# design.net
KiCad netlist of a schematic drawn in Altium Designer
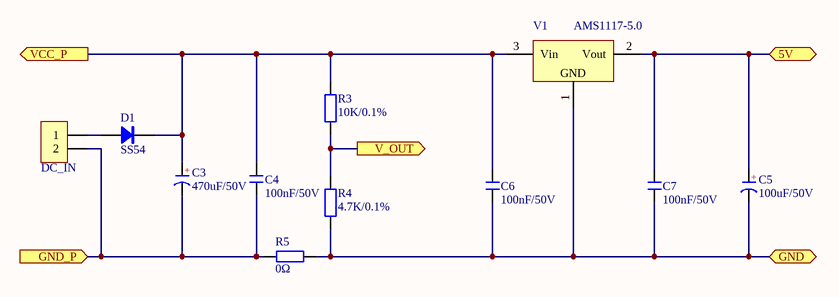
[diagram p0: 电机电源输入原理图.SchDoc]

(export (version "E")
  (design (tool "Eeschema 10.0.6"))
  (components
    (comp (ref "C3")
      (value "470uF/50V")
      (footprint "CAP 5.0*12.5*20")
      (description "直插电解电容")
      (fields (field (name "版权归属") "源创客"))
      (libsource (lib "3.1   - 电阻-电容-电感") (part "C-CAP"))
    )
    (comp (ref "C4")
      (value "100nF/50V")
      (footprint "C 0603_M")
      (description "无极性贴片电容")
      (fields (field (name "版权归属") "源创客"))
      (libsource (lib "3.1   - 电阻-电容-电感") (part "C"))
    )
    (comp (ref "C5")
      (value "100uF/50V")
      (footprint "CAP 3.5*8*11.5")
      (description "直插电解电容")
      (fields (field (name "版权归属") "源创客"))
      (libsource (lib "3.1   - 电阻-电容-电感") (part "C-CAP"))
    )
    (comp (ref "C6")
      (value "100nF/50V")
      (footprint "C 0603_M")
      (description "无极性贴片电容")
      (fields (field (name "版权归属") "源创客"))
      (libsource (lib "3.1   - 电阻-电容-电感") (part "C"))
    )
    (comp (ref "C7")
      (value "100nF/50V")
      (footprint "C 0603_M")
      (description "无极性贴片电容")
      (fields (field (name "版权归属") "源创客"))
      (libsource (lib "3.1   - 电阻-电容-电感") (part "C"))
    )
    (comp (ref "D1")
      (value "SS54")
      (footprint "SMA")
      (description "肖特基二极管")
      (fields (field (name "版权归属") "源创客"))
      (libsource (lib "8.1   - 二极管-整流桥") (part "SS24"))
    )
    (comp (ref "DC_IN")
      (value "HDR-1X2")
      (footprint "XT30PW-M公头")
      (description "2P接插件")
      (fields (field (name "版权归属") "源创客"))
      (libsource (lib "4.10 - 接插件-脚距5.0") (part "Header 2"))
    )
    (comp (ref "R3")
      (value "10K/0.1%")
      (footprint "R 0603_M")
      (description "贴片电阻")
      (fields (field (name "版权归属") "源创客"))
      (libsource (lib "3.1   - 电阻-电容-电感") (part "R"))
    )
    (comp (ref "R4")
      (value "4.7K/0.1%")
      (footprint "R 0603_M")
      (description "贴片电阻")
      (fields (field (name "版权归属") "源创客"))
      (libsource (lib "3.1   - 电阻-电容-电感") (part "R"))
    )
    (comp (ref "R5")
      (value "0Ω")
      (footprint "R 0805_M")
      (description "贴片电阻")
      (fields (field (name "版权归属") "源创客"))
      (libsource (lib "3.1   - 电阻-电容-电感") (part "R"))
    )
    (comp (ref "V1")
      (value "AMS1117-5.0")
      (footprint "SOT89_N")
      (description "三端稳压芯片")
      (fields (field (name "版权归属") "源创客"))
      (libsource (lib "1.3   - 电源类芯片") (part "AMS1117"))
    )
  )
  (nets
    (net (code "1") (name "/5V") (class "Default")
      (node (ref "C5") (pin "1") (pinfunction "A_1") (pintype "passive"))
      (node (ref "C7") (pin "2") (pinfunction "2_2") (pintype "passive"))
      (node (ref "V1") (pin "2") (pinfunction "Vout_2") (pintype "passive"))
    )
    (net (code "2") (name "/GND") (class "Default")
      (node (ref "C5") (pin "2") (pinfunction "K_2") (pintype "passive"))
      (node (ref "C6") (pin "1") (pinfunction "1_1") (pintype "passive"))
      (node (ref "C7") (pin "1") (pinfunction "1_1") (pintype "passive"))
      (node (ref "R4") (pin "1") (pinfunction "1_1") (pintype "passive"))
      (node (ref "R5") (pin "1") (pinfunction "1_1") (pintype "passive"))
      (node (ref "V1") (pin "1") (pinfunction "GND_1") (pintype "passive"))
    )
    (net (code "3") (name "/GND_P") (class "Default")
      (node (ref "C3") (pin "2") (pinfunction "K_2") (pintype "passive"))
      (node (ref "C4") (pin "1") (pinfunction "1_1") (pintype "passive"))
      (node (ref "DC_IN") (pin "2") (pinfunction "2_2") (pintype "passive"))
      (node (ref "R5") (pin "2") (pinfunction "2_2") (pintype "passive"))
    )
    (net (code "4") (name "/VCC_P") (class "Default")
      (node (ref "C3") (pin "1") (pinfunction "A_1") (pintype "passive"))
      (node (ref "C4") (pin "2") (pinfunction "2_2") (pintype "passive"))
      (node (ref "C6") (pin "2") (pinfunction "2_2") (pintype "passive"))
      (node (ref "D1") (pin "2") (pinfunction "K_2") (pintype "passive"))
      (node (ref "R3") (pin "2") (pinfunction "2_2") (pintype "passive"))
      (node (ref "V1") (pin "3") (pinfunction "Vin_3") (pintype "passive"))
    )
    (net (code "5") (name "/V_OUT") (class "Default")
      (node (ref "R3") (pin "1") (pinfunction "1_1") (pintype "passive"))
      (node (ref "R4") (pin "2") (pinfunction "2_2") (pintype "passive"))
    )
    (net (code "6") (name "Net-(D1-A)") (class "Default")
      (node (ref "D1") (pin "1") (pinfunction "A_1") (pintype "passive"))
      (node (ref "DC_IN") (pin "1") (pinfunction "1_1") (pintype "passive"))
    )
  )
)
